# CC2541Dev_board.net
KiCad netlist of a schematic drawn in Altium Designer
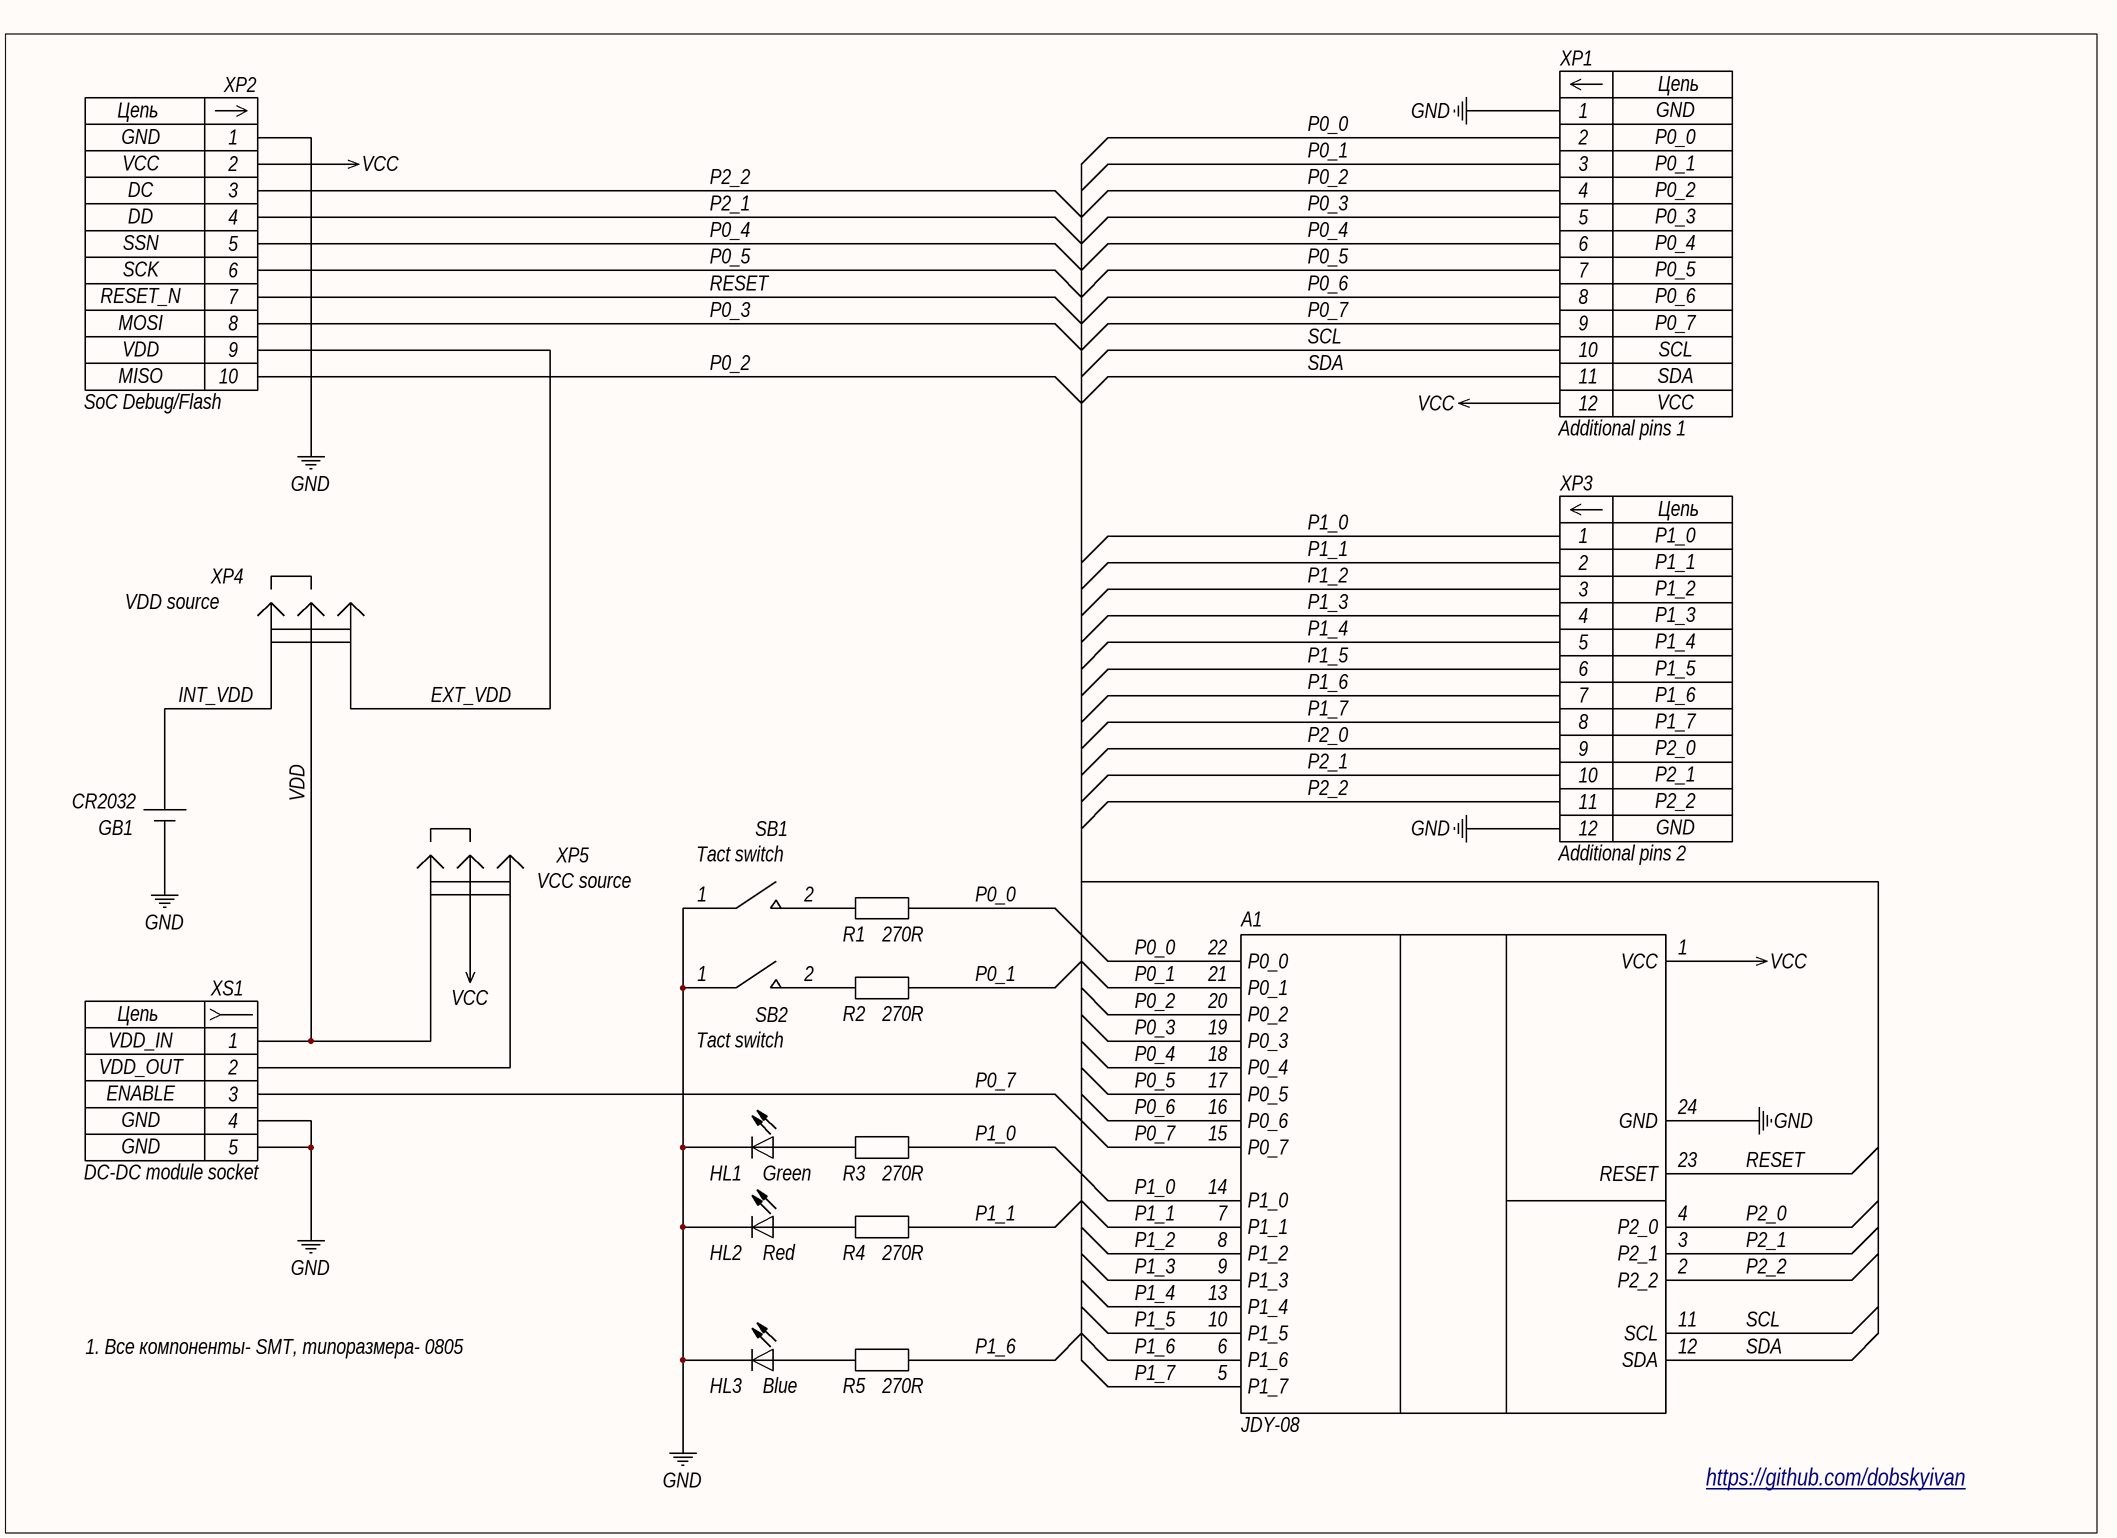
[diagram p0: CC2541Dev_board.SchDoc]

(export (version "E")
  (design (tool "Eeschema 10.0.6"))
  (components
    (comp (ref "A1")
      (value "JDY-08")
      (footprint "JDY-08")
      (description "Модуль BLE, на базе МК CC2541")
      (libsource (lib "My") (part "JDY-08"))
    )
    (comp (ref "GB1")
      (value "CR2032")
      (footprint "S8421R")
      (description "Батарея")
      (libsource (lib "My") (part "BAT"))
    )
    (comp (ref "HL1")
      (value "Green")
      (footprint "LED_0805_GREEN")
      (description "Светодиод, прибор световой сигнализации")
      (libsource (lib "My") (part "DIODE_LED"))
    )
    (comp (ref "HL2")
      (value "Red")
      (footprint "LED_0805_GREEN")
      (description "Светодиод, прибор световой сигнализации")
      (libsource (lib "My") (part "DIODE_LED"))
    )
    (comp (ref "HL3")
      (value "Blue")
      (footprint "LED_0805_GREEN")
      (description "Светодиод, прибор световой сигнализации")
      (libsource (lib "My") (part "DIODE_LED"))
    )
    (comp (ref "R1") (value "270R") (footprint "RES_0805") (libsource (lib "My") (part "RESISTOR")))
    (comp (ref "R2") (value "270R") (footprint "RES_0805") (libsource (lib "My") (part "RESISTOR")))
    (comp (ref "R3") (value "270R") (footprint "RES_0805") (libsource (lib "My") (part "RESISTOR")))
    (comp (ref "R4") (value "270R") (footprint "RES_0805") (libsource (lib "My") (part "RESISTOR")))
    (comp (ref "R5") (value "270R") (footprint "RES_0805") (libsource (lib "My") (part "RESISTOR")))
    (comp (ref "SB1")
      (value "Tact switch")
      (footprint "KLS7-TS6601-5.0-180")
      (libsource (lib "My") (part "SWITCH"))
    )
    (comp (ref "SB2")
      (value "Tact switch")
      (footprint "KLS7-TS6601-5.0-180")
      (libsource (lib "My") (part "SWITCH"))
    )
    (comp (ref "XP1")
      (value "Additional pins 1")
      (footprint "PLS12")
      (description "Штырь, 12 контактов")
      (libsource (lib "My") (part "PIN-12"))
    )
    (comp (ref "XP2")
      (value "SoC Debug/Flash")
      (footprint "PLD10")
      (description "Штырь, 10 контактов")
      (libsource (lib "My") (part "PIN-10"))
    )
    (comp (ref "XP3")
      (value "Additional pins 2")
      (footprint "PLS12")
      (description "Штырь, 12 контактов")
      (libsource (lib "My") (part "PIN-12"))
    )
    (comp (ref "XP4")
      (value "VDD source")
      (footprint "PLS3")
      (description "Штырь, 3 контакта\r\n(\"Mode\" переключает внешний вид)")
      (libsource (lib "My") (part "PIN-3"))
    )
    (comp (ref "XP5")
      (value "VCC source")
      (footprint "PLS3")
      (description "Штырь, 3 контакта\r\n(\"Mode\" переключает внешний вид)")
      (libsource (lib "My") (part "PIN-3"))
    )
    (comp (ref "XS1")
      (value "DC-DC module socket")
      (footprint "PAD")
      (description "Гнездо, 5 контактов")
      (libsource (lib "My") (part "SOCKET-5"))
    )
  )
  (nets
    (net (code "1") (name "/EXT_VDD") (class "Default")
      (node (ref "XP2") (pin "9") (pinfunction "9_9") (pintype "passive"))
      (node (ref "XP4") (pin "3") (pinfunction "3_3") (pintype "passive"))
    )
    (net (code "2") (name "/INT_VDD") (class "Default")
      (node (ref "GB1") (pin "1") (pintype "passive"))
      (node (ref "XP4") (pin "1") (pinfunction "1_1") (pintype "passive"))
    )
    (net (code "3") (name "/P0_0") (class "Default")
      (node (ref "A1") (pin "22") (pinfunction "P0_0_22") (pintype "passive"))
      (node (ref "R1") (pin "2") (pintype "passive"))
      (node (ref "XP1") (pin "2") (pinfunction "2_2") (pintype "passive"))
    )
    (net (code "4") (name "/P0_1") (class "Default")
      (node (ref "A1") (pin "21") (pinfunction "P0_1_21") (pintype "passive"))
      (node (ref "R2") (pin "2") (pintype "passive"))
      (node (ref "XP1") (pin "3") (pinfunction "3_3") (pintype "passive"))
    )
    (net (code "5") (name "/P0_2") (class "Default")
      (node (ref "A1") (pin "20") (pinfunction "P0_2_20") (pintype "passive"))
      (node (ref "XP1") (pin "4") (pinfunction "4_4") (pintype "passive"))
      (node (ref "XP2") (pin "10") (pinfunction "10_10") (pintype "passive"))
    )
    (net (code "6") (name "/P0_3") (class "Default")
      (node (ref "A1") (pin "19") (pinfunction "P0_3_19") (pintype "passive"))
      (node (ref "XP1") (pin "5") (pinfunction "5_5") (pintype "passive"))
      (node (ref "XP2") (pin "8") (pinfunction "8_8") (pintype "passive"))
    )
    (net (code "7") (name "/P0_4") (class "Default")
      (node (ref "A1") (pin "18") (pinfunction "P0_4_18") (pintype "passive"))
      (node (ref "XP1") (pin "6") (pinfunction "6_6") (pintype "passive"))
      (node (ref "XP2") (pin "5") (pinfunction "5_5") (pintype "passive"))
    )
    (net (code "8") (name "/P0_5") (class "Default")
      (node (ref "A1") (pin "17") (pinfunction "P0_5_17") (pintype "passive"))
      (node (ref "XP1") (pin "7") (pinfunction "7_7") (pintype "passive"))
      (node (ref "XP2") (pin "6") (pinfunction "6_6") (pintype "passive"))
    )
    (net (code "9") (name "/P0_6") (class "Default")
      (node (ref "A1") (pin "16") (pinfunction "P0_6_16") (pintype "passive"))
      (node (ref "XP1") (pin "8") (pinfunction "8_8") (pintype "passive"))
    )
    (net (code "10") (name "/P0_7") (class "Default")
      (node (ref "A1") (pin "15") (pinfunction "P0_7_15") (pintype "passive"))
      (node (ref "XP1") (pin "9") (pinfunction "9_9") (pintype "passive"))
      (node (ref "XS1") (pin "3") (pinfunction "3_3") (pintype "passive"))
    )
    (net (code "11") (name "/P1_0") (class "Default")
      (node (ref "A1") (pin "14") (pinfunction "P1_0_14") (pintype "passive"))
      (node (ref "R3") (pin "2") (pintype "passive"))
      (node (ref "XP3") (pin "1") (pinfunction "1_1") (pintype "passive"))
    )
    (net (code "12") (name "/P1_1") (class "Default")
      (node (ref "A1") (pin "7") (pinfunction "P1_1_7") (pintype "passive"))
      (node (ref "R4") (pin "2") (pintype "passive"))
      (node (ref "XP3") (pin "2") (pinfunction "2_2") (pintype "passive"))
    )
    (net (code "13") (name "/P1_2") (class "Default")
      (node (ref "A1") (pin "8") (pinfunction "P1_2_8") (pintype "passive"))
      (node (ref "XP3") (pin "3") (pinfunction "3_3") (pintype "passive"))
    )
    (net (code "14") (name "/P1_3") (class "Default")
      (node (ref "A1") (pin "9") (pinfunction "P1_3_9") (pintype "passive"))
      (node (ref "XP3") (pin "4") (pinfunction "4_4") (pintype "passive"))
    )
    (net (code "15") (name "/P1_4") (class "Default")
      (node (ref "A1") (pin "13") (pinfunction "P1_4_13") (pintype "passive"))
      (node (ref "XP3") (pin "5") (pinfunction "5_5") (pintype "passive"))
    )
    (net (code "16") (name "/P1_5") (class "Default")
      (node (ref "A1") (pin "10") (pinfunction "P1_5_10") (pintype "passive"))
      (node (ref "XP3") (pin "6") (pinfunction "6_6") (pintype "passive"))
    )
    (net (code "17") (name "/P1_6") (class "Default")
      (node (ref "A1") (pin "6") (pinfunction "P1_6_6") (pintype "passive"))
      (node (ref "R5") (pin "2") (pintype "passive"))
      (node (ref "XP3") (pin "7") (pinfunction "7_7") (pintype "passive"))
    )
    (net (code "18") (name "/P1_7") (class "Default")
      (node (ref "A1") (pin "5") (pinfunction "P1_7_5") (pintype "passive"))
      (node (ref "XP3") (pin "8") (pinfunction "8_8") (pintype "passive"))
    )
    (net (code "19") (name "/P2_0") (class "Default")
      (node (ref "A1") (pin "4") (pinfunction "P2_0_4") (pintype "passive"))
      (node (ref "XP3") (pin "9") (pinfunction "9_9") (pintype "passive"))
    )
    (net (code "20") (name "/P2_1") (class "Default")
      (node (ref "A1") (pin "3") (pinfunction "P2_1_3") (pintype "passive"))
      (node (ref "XP2") (pin "4") (pinfunction "4_4") (pintype "passive"))
      (node (ref "XP3") (pin "10") (pinfunction "10_10") (pintype "passive"))
    )
    (net (code "21") (name "/P2_2") (class "Default")
      (node (ref "A1") (pin "2") (pinfunction "P2_2_2") (pintype "passive"))
      (node (ref "XP2") (pin "3") (pinfunction "3_3") (pintype "passive"))
      (node (ref "XP3") (pin "11") (pinfunction "11_11") (pintype "passive"))
    )
    (net (code "22") (name "/RESET") (class "Default")
      (node (ref "A1") (pin "23") (pinfunction "RESET_23") (pintype "passive"))
      (node (ref "XP2") (pin "7") (pinfunction "7_7") (pintype "passive"))
    )
    (net (code "23") (name "/SCL") (class "Default")
      (node (ref "A1") (pin "11") (pinfunction "SCL_11") (pintype "passive"))
      (node (ref "XP1") (pin "10") (pinfunction "10_10") (pintype "passive"))
    )
    (net (code "24") (name "/SDA") (class "Default")
      (node (ref "A1") (pin "12") (pinfunction "SDA_12") (pintype "passive"))
      (node (ref "XP1") (pin "11") (pinfunction "11_11") (pintype "passive"))
    )
    (net (code "25") (name "/VDD") (class "Default")
      (node (ref "XP4") (pin "2") (pinfunction "2_2") (pintype "passive"))
      (node (ref "XP5") (pin "1") (pinfunction "1_1") (pintype "passive"))
      (node (ref "XS1") (pin "1") (pinfunction "1_1") (pintype "passive"))
    )
    (net (code "26") (name "GND") (class "Default")
      (node (ref "A1") (pin "24") (pinfunction "GND_24") (pintype "passive"))
      (node (ref "GB1") (pin "2") (pintype "passive"))
      (node (ref "HL1") (pin "2") (pinfunction "2_2") (pintype "passive"))
      (node (ref "HL2") (pin "2") (pinfunction "2_2") (pintype "passive"))
      (node (ref "HL3") (pin "2") (pinfunction "2_2") (pintype "passive"))
      (node (ref "SB1") (pin "1") (pinfunction "MR_1") (pintype "passive"))
      (node (ref "SB2") (pin "1") (pinfunction "MR_1") (pintype "passive"))
      (node (ref "XP1") (pin "1") (pinfunction "1_1") (pintype "passive"))
      (node (ref "XP2") (pin "1") (pinfunction "1_1") (pintype "passive"))
      (node (ref "XP3") (pin "12") (pinfunction "12_12") (pintype "passive"))
      (node (ref "XS1") (pin "4") (pinfunction "4_4") (pintype "passive"))
      (node (ref "XS1") (pin "5") (pinfunction "5_5") (pintype "passive"))
    )
    (net (code "27") (name "Net-(HL1-Pad1)") (class "Default")
      (node (ref "HL1") (pin "1") (pinfunction "1_1") (pintype "passive"))
      (node (ref "R3") (pin "1") (pintype "passive"))
    )
    (net (code "28") (name "Net-(HL2-Pad1)") (class "Default")
      (node (ref "HL2") (pin "1") (pinfunction "1_1") (pintype "passive"))
      (node (ref "R4") (pin "1") (pintype "passive"))
    )
    (net (code "29") (name "Net-(HL3-Pad1)") (class "Default")
      (node (ref "HL3") (pin "1") (pinfunction "1_1") (pintype "passive"))
      (node (ref "R5") (pin "1") (pintype "passive"))
    )
    (net (code "30") (name "Net-(R1-Pad1)") (class "Default")
      (node (ref "R1") (pin "1") (pintype "passive"))
      (node (ref "SB1") (pin "2") (pinfunction "MR_2") (pintype "passive"))
    )
    (net (code "31") (name "Net-(R2-Pad1)") (class "Default")
      (node (ref "R2") (pin "1") (pintype "passive"))
      (node (ref "SB2") (pin "2") (pinfunction "MR_2") (pintype "passive"))
    )
    (net (code "32") (name "Net-(XP5-Pad3)") (class "Default")
      (node (ref "XP5") (pin "3") (pinfunction "3_3") (pintype "passive"))
      (node (ref "XS1") (pin "2") (pinfunction "2_2") (pintype "passive"))
    )
    (net (code "33") (name "VCC") (class "Default")
      (node (ref "A1") (pin "1") (pinfunction "VCC_1") (pintype "passive"))
      (node (ref "XP1") (pin "12") (pinfunction "12_12") (pintype "passive"))
      (node (ref "XP2") (pin "2") (pinfunction "2_2") (pintype "passive"))
      (node (ref "XP5") (pin "2") (pinfunction "2_2") (pintype "passive"))
    )
  )
)
